# main.net
KiCad netlist of a schematic drawn in Altium Designer
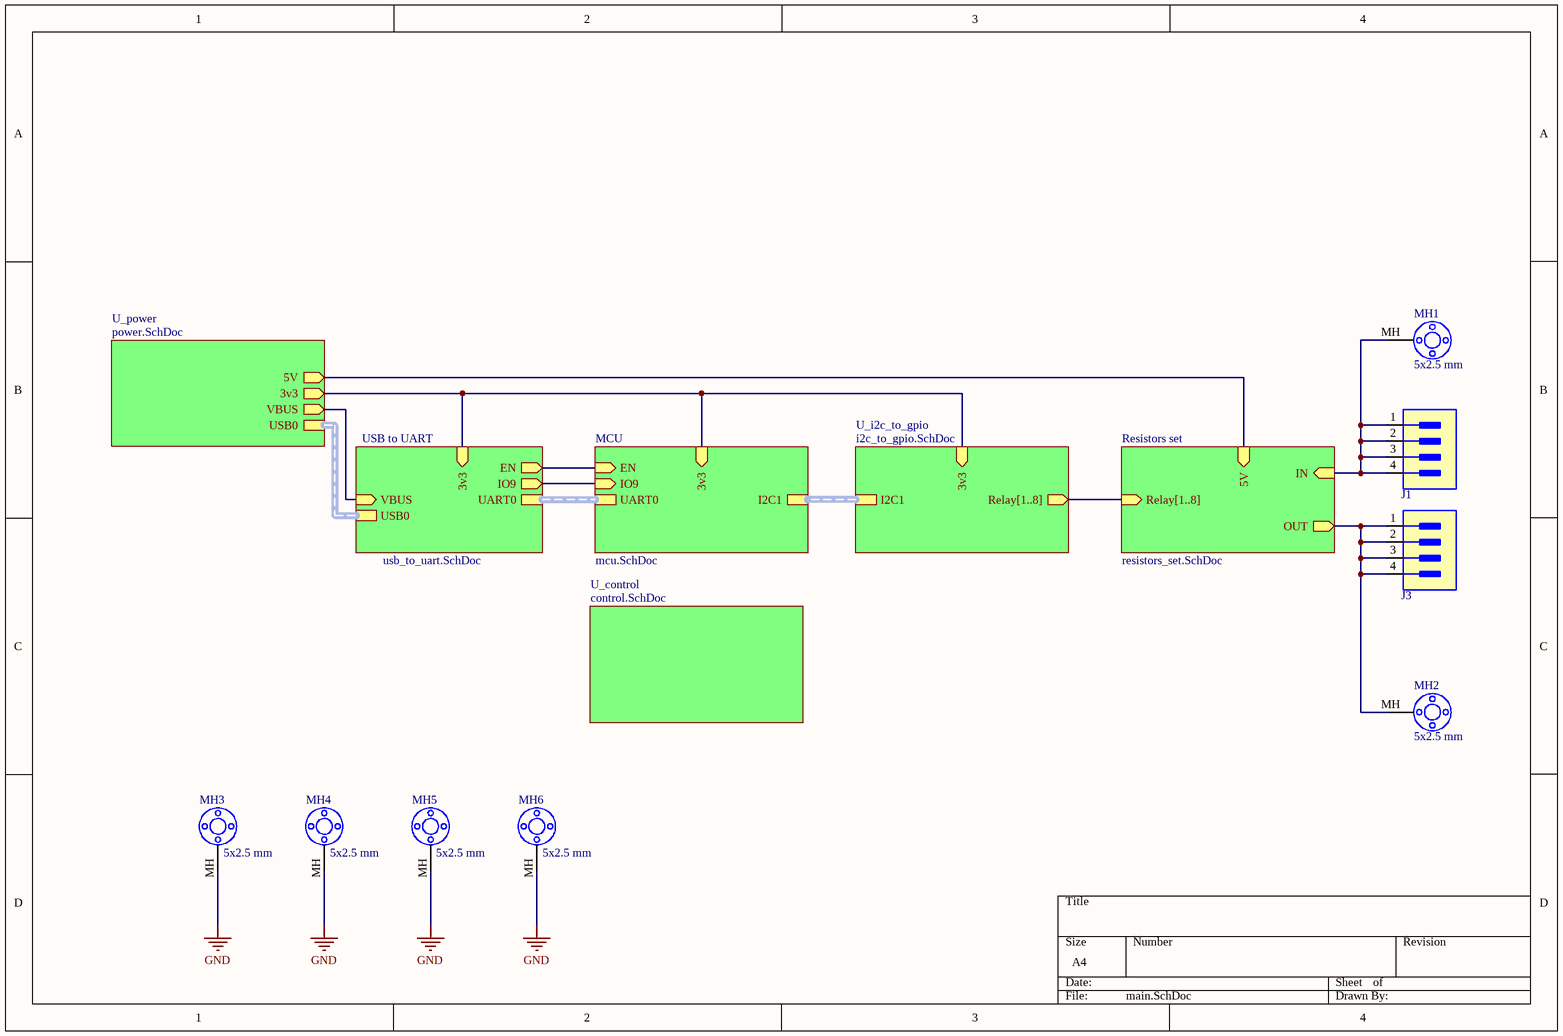
[diagram p0: main.SchDoc]

(export (version "E")
  (design (tool "Eeschema 10.0.6"))
  (components
    (comp (ref "J1")
      (value "PM254-2-02-Z-8.5")
      (footprint "254-2-2-Fem")
      (fields (field (name "MANUFACTURER") "HCTL"))
      (libsource (lib "Lib_Kam") (part "Header_4"))
    )
    (comp (ref "J3")
      (value "PM254-2-02-Z-8.5")
      (footprint "254-2-2-Fem")
      (fields (field (name "MANUFACTURER") "HCTL"))
      (libsource (lib "Lib_Kam") (part "Header_4"))
    )
    (comp (ref "MH1")
      (value "5x2.5 mm")
      (footprint "5x2m7_plated_hole")
      (description "Plated hole 5x2.5 mm")
      (fields (field (name "PART NUMBER") "none"))
      (libsource (lib "Lib_Kam") (part "Plated_hole"))
    )
    (comp (ref "MH2")
      (value "5x2.5 mm")
      (footprint "5x2m7_plated_hole")
      (description "Plated hole 5x2.5 mm")
      (fields (field (name "PART NUMBER") "none"))
      (libsource (lib "Lib_Kam") (part "Plated_hole"))
    )
    (comp (ref "MH3")
      (value "5x2.5 mm")
      (footprint "5x2m7_plated_hole")
      (description "Plated hole 5x2.5 mm")
      (fields (field (name "PART NUMBER") "none"))
      (libsource (lib "Lib_Kam") (part "Plated_hole"))
    )
    (comp (ref "MH4")
      (value "5x2.5 mm")
      (footprint "5x2m7_plated_hole")
      (description "Plated hole 5x2.5 mm")
      (fields (field (name "PART NUMBER") "none"))
      (libsource (lib "Lib_Kam") (part "Plated_hole"))
    )
    (comp (ref "MH5")
      (value "5x2.5 mm")
      (footprint "5x2m7_plated_hole")
      (description "Plated hole 5x2.5 mm")
      (fields (field (name "PART NUMBER") "none"))
      (libsource (lib "Lib_Kam") (part "Plated_hole"))
    )
    (comp (ref "MH6")
      (value "5x2.5 mm")
      (footprint "5x2m7_plated_hole")
      (description "Plated hole 5x2.5 mm")
      (fields (field (name "PART NUMBER") "none"))
      (libsource (lib "Lib_Kam") (part "Plated_hole"))
    )
  )
  (nets
    (net (code "5") (name "/IN") (class "Default")
      (node (ref "J1") (pin "1") (pinfunction "1_1") (pintype "passive"))
      (node (ref "J1") (pin "2") (pinfunction "2_2") (pintype "passive"))
      (node (ref "J1") (pin "3") (pinfunction "3_3") (pintype "passive"))
      (node (ref "J1") (pin "4") (pinfunction "4_4") (pintype "passive"))
      (node (ref "MH1") (pin "MH") (pinfunction "MH_MH") (pintype "passive"))
    )
    (net (code "7") (name "/OUT") (class "Default")
      (node (ref "J3") (pin "1") (pinfunction "1_1") (pintype "passive"))
      (node (ref "J3") (pin "2") (pinfunction "2_2") (pintype "passive"))
      (node (ref "J3") (pin "3") (pinfunction "3_3") (pintype "passive"))
      (node (ref "J3") (pin "4") (pinfunction "4_4") (pintype "passive"))
      (node (ref "MH2") (pin "MH") (pinfunction "MH_MH") (pintype "passive"))
    )
    (net (code "12") (name "GND") (class "Default")
      (node (ref "MH3") (pin "MH") (pinfunction "MH_MH") (pintype "passive"))
      (node (ref "MH4") (pin "MH") (pinfunction "MH_MH") (pintype "passive"))
      (node (ref "MH5") (pin "MH") (pinfunction "MH_MH") (pintype "passive"))
      (node (ref "MH6") (pin "MH") (pinfunction "MH_MH") (pintype "passive"))
    )
  )
)
